# full_bridge_driver.net
KiCad netlist of a schematic drawn in EAGLE
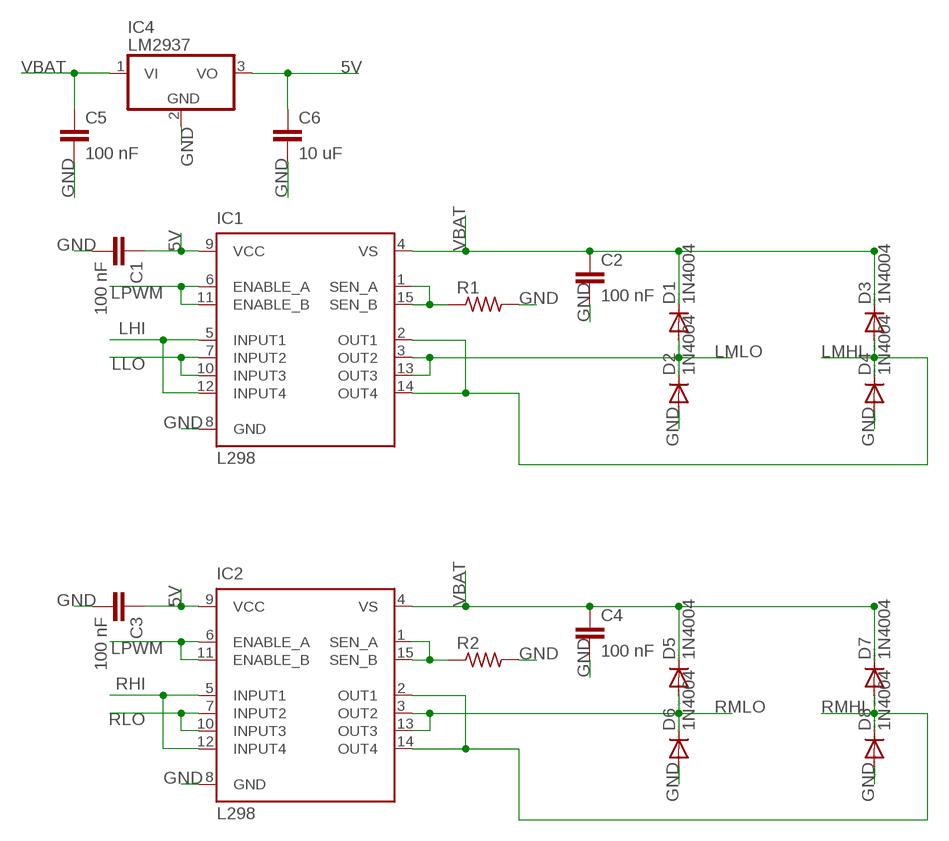
[diagram p0: schematic, sheet 1]

(export (version "E")
  (design (tool "Eeschema 10.0.6"))
  (components
    (comp (ref "C1")
      (value "100 nF")
      (footprint "eagle-import:C0603")
      (libsource (lib "eagle-import") (part "C-EUC0603"))
    )
    (comp (ref "C2")
      (value "100 nF")
      (footprint "eagle-import:C0603")
      (libsource (lib "eagle-import") (part "C-EUC0603"))
    )
    (comp (ref "C3")
      (value "100 nF")
      (footprint "eagle-import:C0603")
      (libsource (lib "eagle-import") (part "C-EUC0603"))
    )
    (comp (ref "C4")
      (value "100 nF")
      (footprint "eagle-import:C0603")
      (libsource (lib "eagle-import") (part "C-EUC0603"))
    )
    (comp (ref "C5")
      (value "100 nF")
      (footprint "eagle-import:C0603")
      (libsource (lib "eagle-import") (part "C-EUC0603"))
    )
    (comp (ref "C6")
      (value "10 uF")
      (footprint "eagle-import:C0603")
      (libsource (lib "eagle-import") (part "C-EUC0603"))
    )
    (comp (ref "D1")
      (value "1N4004")
      (footprint "eagle-import:DO41-10")
      (libsource (lib "eagle-import") (part "1N4004"))
    )
    (comp (ref "D2")
      (value "1N4004")
      (footprint "eagle-import:DO41-10")
      (libsource (lib "eagle-import") (part "1N4004"))
    )
    (comp (ref "D3")
      (value "1N4004")
      (footprint "eagle-import:DO41-10")
      (libsource (lib "eagle-import") (part "1N4004"))
    )
    (comp (ref "D4")
      (value "1N4004")
      (footprint "eagle-import:DO41-10")
      (libsource (lib "eagle-import") (part "1N4004"))
    )
    (comp (ref "D5")
      (value "1N4004")
      (footprint "eagle-import:DO41-10")
      (libsource (lib "eagle-import") (part "1N4004"))
    )
    (comp (ref "D6")
      (value "1N4004")
      (footprint "eagle-import:DO41-10")
      (libsource (lib "eagle-import") (part "1N4004"))
    )
    (comp (ref "D7")
      (value "1N4004")
      (footprint "eagle-import:DO41-10")
      (libsource (lib "eagle-import") (part "1N4004"))
    )
    (comp (ref "D8")
      (value "1N4004")
      (footprint "eagle-import:DO41-10")
      (libsource (lib "eagle-import") (part "1N4004"))
    )
    (comp (ref "IC1")
      (value "L298")
      (footprint "eagle-import:MULTIWATT-15")
      (fields (field (name "MPN") "L298N"))
      (libsource (lib "eagle-import") (part "L298"))
    )
    (comp (ref "IC2")
      (value "L298")
      (footprint "eagle-import:MULTIWATT-15")
      (fields (field (name "MPN") "L298N"))
      (libsource (lib "eagle-import") (part "L298"))
    )
    (comp (ref "IC4")
      (value "LM2937")
      (footprint "eagle-import:TO263-3")
      (libsource (lib "eagle-import") (part "LM2937"))
    )
    (comp (ref "R1")
      (value "R-US_0204/7")
      (footprint "eagle-import:0204_7")
      (libsource (lib "eagle-import") (part "R-US_0204/7"))
    )
    (comp (ref "R2")
      (value "R-US_0204/7")
      (footprint "eagle-import:0204_7")
      (libsource (lib "eagle-import") (part "R-US_0204/7"))
    )
  )
  (nets
    (net (code "1") (name "/5V") (class "Default")
      (node (ref "C1") (pin "1") (pinfunction "1_1") (pintype "passive"))
      (node (ref "C3") (pin "1") (pinfunction "1_1") (pintype "passive"))
      (node (ref "C6") (pin "1") (pinfunction "1_1") (pintype "passive"))
      (node (ref "IC1") (pin "9") (pinfunction "VCC_9") (pintype "power_in"))
      (node (ref "IC2") (pin "9") (pinfunction "VCC_9") (pintype "power_in"))
      (node (ref "IC4") (pin "3") (pinfunction "VO_3") (pintype "passive"))
    )
    (net (code "2") (name "/GND") (class "Default")
      (node (ref "C1") (pin "2") (pinfunction "2_2") (pintype "passive"))
      (node (ref "C2") (pin "2") (pinfunction "2_2") (pintype "passive"))
      (node (ref "C3") (pin "2") (pinfunction "2_2") (pintype "passive"))
      (node (ref "C4") (pin "2") (pinfunction "2_2") (pintype "passive"))
      (node (ref "C5") (pin "2") (pinfunction "2_2") (pintype "passive"))
      (node (ref "C6") (pin "2") (pinfunction "2_2") (pintype "passive"))
      (node (ref "D2") (pin "A") (pinfunction "A_A") (pintype "passive"))
      (node (ref "D4") (pin "A") (pinfunction "A_A") (pintype "passive"))
      (node (ref "D6") (pin "A") (pinfunction "A_A") (pintype "passive"))
      (node (ref "D8") (pin "A") (pinfunction "A_A") (pintype "passive"))
      (node (ref "IC1") (pin "8") (pinfunction "GND_8") (pintype "power_in"))
      (node (ref "IC2") (pin "8") (pinfunction "GND_8") (pintype "power_in"))
      (node (ref "IC4") (pin "2") (pinfunction "GND_2") (pintype "passive"))
      (node (ref "R1") (pin "2") (pinfunction "2_2") (pintype "passive"))
      (node (ref "R2") (pin "2") (pinfunction "2_2") (pintype "passive"))
    )
    (net (code "3") (name "/LHI") (class "Default")
      (node (ref "IC1") (pin "12") (pinfunction "INPUT4_12") (pintype "input"))
      (node (ref "IC1") (pin "5") (pinfunction "INPUT1_5") (pintype "input"))
    )
    (net (code "4") (name "/LLO") (class "Default")
      (node (ref "IC1") (pin "10") (pinfunction "INPUT3_10") (pintype "input"))
      (node (ref "IC1") (pin "7") (pinfunction "INPUT2_7") (pintype "input"))
    )
    (net (code "5") (name "/LMHI") (class "Default")
      (node (ref "D3") (pin "A") (pinfunction "A_A") (pintype "passive"))
      (node (ref "D4") (pin "C") (pinfunction "C_C") (pintype "passive"))
      (node (ref "IC1") (pin "14") (pinfunction "OUT4_14") (pintype "output"))
      (node (ref "IC1") (pin "2") (pinfunction "OUT1_2") (pintype "output"))
    )
    (net (code "6") (name "/LMLO") (class "Default")
      (node (ref "D1") (pin "A") (pinfunction "A_A") (pintype "passive"))
      (node (ref "D2") (pin "C") (pinfunction "C_C") (pintype "passive"))
      (node (ref "IC1") (pin "13") (pinfunction "OUT3_13") (pintype "output"))
      (node (ref "IC1") (pin "3") (pinfunction "OUT2_3") (pintype "output"))
    )
    (net (code "7") (name "/LPWM") (class "Default")
      (node (ref "IC1") (pin "11") (pinfunction "ENABLE_B_11") (pintype "input"))
      (node (ref "IC1") (pin "6") (pinfunction "ENABLE_A_6") (pintype "input"))
      (node (ref "IC2") (pin "11") (pinfunction "ENABLE_B_11") (pintype "input"))
      (node (ref "IC2") (pin "6") (pinfunction "ENABLE_A_6") (pintype "input"))
    )
    (net (code "8") (name "/RHI") (class "Default")
      (node (ref "IC2") (pin "12") (pinfunction "INPUT4_12") (pintype "input"))
      (node (ref "IC2") (pin "5") (pinfunction "INPUT1_5") (pintype "input"))
    )
    (net (code "9") (name "/RLO") (class "Default")
      (node (ref "IC2") (pin "10") (pinfunction "INPUT3_10") (pintype "input"))
      (node (ref "IC2") (pin "7") (pinfunction "INPUT2_7") (pintype "input"))
    )
    (net (code "10") (name "/RMHI") (class "Default")
      (node (ref "D7") (pin "A") (pinfunction "A_A") (pintype "passive"))
      (node (ref "D8") (pin "C") (pinfunction "C_C") (pintype "passive"))
      (node (ref "IC2") (pin "14") (pinfunction "OUT4_14") (pintype "output"))
      (node (ref "IC2") (pin "2") (pinfunction "OUT1_2") (pintype "output"))
    )
    (net (code "11") (name "/RMLO") (class "Default")
      (node (ref "D5") (pin "A") (pinfunction "A_A") (pintype "passive"))
      (node (ref "D6") (pin "C") (pinfunction "C_C") (pintype "passive"))
      (node (ref "IC2") (pin "13") (pinfunction "OUT3_13") (pintype "output"))
      (node (ref "IC2") (pin "3") (pinfunction "OUT2_3") (pintype "output"))
    )
    (net (code "12") (name "/VBAT") (class "Default")
      (node (ref "C2") (pin "1") (pinfunction "1_1") (pintype "passive"))
      (node (ref "C4") (pin "1") (pinfunction "1_1") (pintype "passive"))
      (node (ref "C5") (pin "1") (pinfunction "1_1") (pintype "passive"))
      (node (ref "D1") (pin "C") (pinfunction "C_C") (pintype "passive"))
      (node (ref "D3") (pin "C") (pinfunction "C_C") (pintype "passive"))
      (node (ref "D5") (pin "C") (pinfunction "C_C") (pintype "passive"))
      (node (ref "D7") (pin "C") (pinfunction "C_C") (pintype "passive"))
      (node (ref "IC1") (pin "4") (pinfunction "VS_4") (pintype "power_in"))
      (node (ref "IC2") (pin "4") (pinfunction "VS_4") (pintype "power_in"))
      (node (ref "IC4") (pin "1") (pinfunction "VI_1") (pintype "input"))
    )
    (net (code "13") (name "Net-(IC1-SEN_A)") (class "Default")
      (node (ref "IC1") (pin "1") (pinfunction "SEN_A_1") (pintype "input"))
      (node (ref "IC1") (pin "15") (pinfunction "SEN_B_15") (pintype "input"))
      (node (ref "R1") (pin "1") (pinfunction "1_1") (pintype "passive"))
    )
    (net (code "14") (name "Net-(IC2-SEN_A)") (class "Default")
      (node (ref "IC2") (pin "1") (pinfunction "SEN_A_1") (pintype "input"))
      (node (ref "IC2") (pin "15") (pinfunction "SEN_B_15") (pintype "input"))
      (node (ref "R2") (pin "1") (pinfunction "1_1") (pintype "passive"))
    )
  )
)
